# Modul.net
KiCad netlist of a schematic drawn in EAGLE
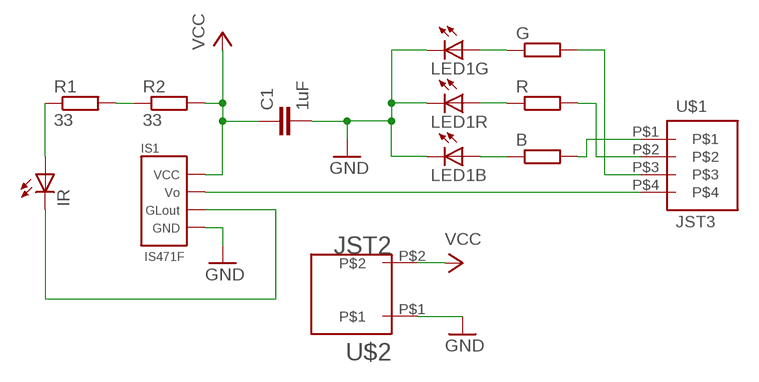
[diagram p0: schematic, sheet 1]

(export (version "E")
  (design (tool "Eeschema 10.0.6"))
  (components
    (comp (ref "B")
      (value "R-EU_R1206")
      (footprint "eagle-import:R1206")
      (libsource (lib "eagle-import") (part "R-EU_R1206"))
    )
    (comp (ref "C1")
      (value "1uF")
      (footprint "eagle-import:C1206")
      (libsource (lib "eagle-import") (part "C-EUC1206"))
    )
    (comp (ref "G")
      (value "R-EU_R1206")
      (footprint "eagle-import:R1206")
      (libsource (lib "eagle-import") (part "R-EU_R1206"))
    )
    (comp (ref "IR")
      (value "LEDSML1206")
      (footprint "eagle-import:SML1206")
      (libsource (lib "eagle-import") (part "LEDSML1206"))
    )
    (comp (ref "IS1")
      (value "IS471F")
      (footprint "eagle-import:IS471F")
      (libsource (lib "eagle-import") (part "IS471F"))
    )
    (comp (ref "LED1")
      (value "LP2C63-ST-RGB-SR0")
      (footprint "eagle-import:LP2C63-ST-RGB-SR0")
      (libsource (lib "eagle-import") (part "LP2C63-ST-RGB-SR0"))
    )
    (comp (ref "R")
      (value "R-EU_R1206")
      (footprint "eagle-import:R1206")
      (libsource (lib "eagle-import") (part "R-EU_R1206"))
    )
    (comp (ref "R1")
      (value "33")
      (footprint "eagle-import:R1206")
      (libsource (lib "eagle-import") (part "R-EU_R1206"))
    )
    (comp (ref "R2")
      (value "33")
      (footprint "eagle-import:R1206")
      (libsource (lib "eagle-import") (part "R-EU_R1206"))
    )
    (comp (ref "U$1")
      (value "JST3")
      (footprint "eagle-import:JST")
      (libsource (lib "eagle-import") (part "JST3"))
    )
    (comp (ref "U$2")
      (value "JST2")
      (footprint "eagle-import:JST")
      (libsource (lib "eagle-import") (part "JST2"))
    )
  )
  (nets
    (net (code "1") (name "GND") (class "Default")
      (node (ref "C1") (pin "2") (pinfunction "2_2") (pintype "passive"))
      (node (ref "IS1") (pin "P$3") (pinfunction "GND_P$3") (pintype "power_in"))
      (node (ref "LED1") (pin "4") (pinfunction "C_4") (pintype "passive"))
      (node (ref "LED1") (pin "5") (pinfunction "C_5") (pintype "passive"))
      (node (ref "LED1") (pin "6") (pinfunction "C_6") (pintype "passive"))
      (node (ref "U$2") (pin "P$1") (pinfunction "P$1_P$1") (pintype "bidirectional"))
    )
    (net (code "2") (name "Net-(B-Pad2)") (class "Default")
      (node (ref "B") (pin "2") (pinfunction "2_2") (pintype "passive"))
      (node (ref "U$1") (pin "P$1") (pinfunction "P$1_P$1") (pintype "bidirectional"))
    )
    (net (code "3") (name "Net-(G-Pad2)") (class "Default")
      (node (ref "G") (pin "2") (pinfunction "2_2") (pintype "passive"))
      (node (ref "U$1") (pin "P$3") (pinfunction "P$3_P$3") (pintype "bidirectional"))
    )
    (net (code "4") (name "Net-(IR-PadA)") (class "Default")
      (node (ref "IR") (pin "A") (pinfunction "A_A") (pintype "passive"))
      (node (ref "R1") (pin "1") (pinfunction "1_1") (pintype "passive"))
    )
    (net (code "5") (name "Net-(IS1-GL)") (class "Default")
      (node (ref "IR") (pin "C") (pinfunction "C_C") (pintype "passive"))
      (node (ref "IS1") (pin "P$4") (pinfunction "GL_P$4") (pintype "bidirectional"))
    )
    (net (code "6") (name "Net-(IS1-VO)") (class "Default")
      (node (ref "IS1") (pin "P$2") (pinfunction "VO_P$2") (pintype "bidirectional"))
      (node (ref "U$1") (pin "P$4") (pinfunction "P$4_P$4") (pintype "bidirectional"))
    )
    (net (code "7") (name "Net-(LED1A-A)") (class "Default")
      (node (ref "B") (pin "1") (pinfunction "1_1") (pintype "passive"))
      (node (ref "LED1") (pin "3") (pinfunction "A_3") (pintype "passive"))
    )
    (net (code "8") (name "Net-(LED1B-A)") (class "Default")
      (node (ref "G") (pin "1") (pinfunction "1_1") (pintype "passive"))
      (node (ref "LED1") (pin "1") (pinfunction "A_1") (pintype "passive"))
    )
    (net (code "9") (name "Net-(LED1C-A)") (class "Default")
      (node (ref "LED1") (pin "2") (pinfunction "A_2") (pintype "passive"))
      (node (ref "R") (pin "1") (pinfunction "1_1") (pintype "passive"))
    )
    (net (code "10") (name "Net-(R-Pad2)") (class "Default")
      (node (ref "R") (pin "2") (pinfunction "2_2") (pintype "passive"))
      (node (ref "U$1") (pin "P$2") (pinfunction "P$2_P$2") (pintype "bidirectional"))
    )
    (net (code "11") (name "Net-(R1-Pad2)") (class "Default")
      (node (ref "R1") (pin "2") (pinfunction "2_2") (pintype "passive"))
      (node (ref "R2") (pin "1") (pinfunction "1_1") (pintype "passive"))
    )
    (net (code "12") (name "VCC") (class "Default")
      (node (ref "C1") (pin "1") (pinfunction "1_1") (pintype "passive"))
      (node (ref "IS1") (pin "P$1") (pinfunction "VCC_P$1") (pintype "power_in"))
      (node (ref "R2") (pin "2") (pinfunction "2_2") (pintype "passive"))
      (node (ref "U$2") (pin "P$2") (pinfunction "P$2_P$2") (pintype "bidirectional"))
    )
  )
)
